# 12V_power_rail.net
KiCad netlist of a schematic drawn in EAGLE
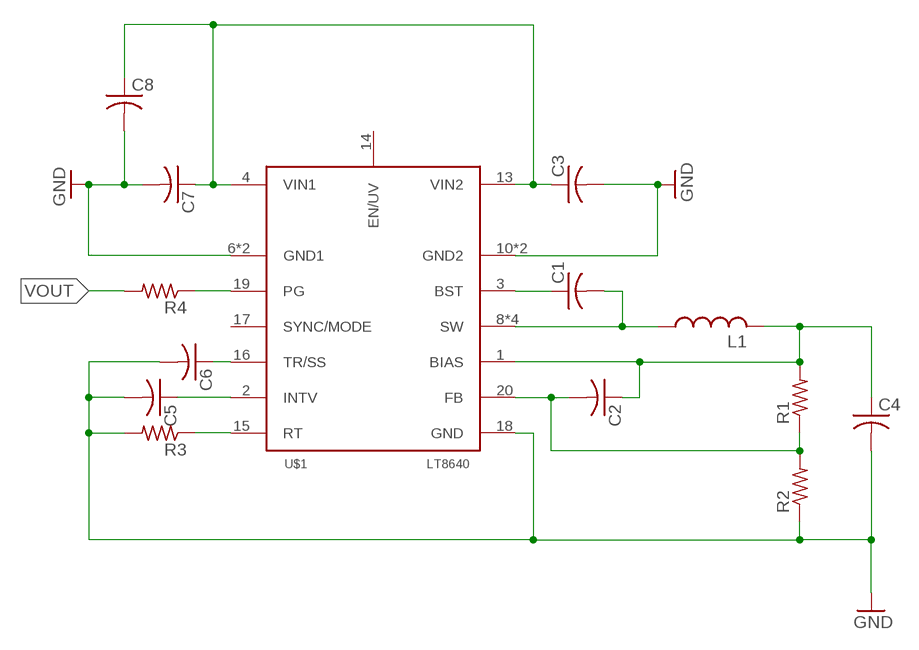
[diagram p0: schematic, sheet 1]

(export (version "E")
  (design (tool "Eeschema 10.0.6"))
  (components
    (comp (ref "C1")
      (value "C-USC0402")
      (footprint "eagle-import:C0402")
      (libsource (lib "eagle-import") (part "C-USC0402"))
    )
    (comp (ref "C2")
      (value "C-USC0402")
      (footprint "eagle-import:C0402")
      (libsource (lib "eagle-import") (part "C-USC0402"))
    )
    (comp (ref "C3")
      (value "C-USC0402")
      (footprint "eagle-import:C0402")
      (libsource (lib "eagle-import") (part "C-USC0402"))
    )
    (comp (ref "C4")
      (value "C-USC1210")
      (footprint "eagle-import:C1210")
      (libsource (lib "eagle-import") (part "C-USC1210"))
    )
    (comp (ref "C5")
      (value "C-USC0402")
      (footprint "eagle-import:C0402")
      (libsource (lib "eagle-import") (part "C-USC0402"))
    )
    (comp (ref "C6")
      (value "C-USC0402")
      (footprint "eagle-import:C0402")
      (libsource (lib "eagle-import") (part "C-USC0402"))
    )
    (comp (ref "C7")
      (value "C-USC0402")
      (footprint "eagle-import:C0402")
      (libsource (lib "eagle-import") (part "C-USC0402"))
    )
    (comp (ref "C8")
      (value "C-USC0603")
      (footprint "eagle-import:C0603")
      (libsource (lib "eagle-import") (part "C-USC0603"))
    )
    (comp (ref "L1")
      (value "L-USIHLP2525EZER4R7M01")
      (footprint "eagle-import:IHLP2525EZER4R7M01-FOOT")
      (libsource (lib "eagle-import") (part "L-USIHLP2525EZER4R7M01"))
    )
    (comp (ref "R1")
      (value "R-US_R0402")
      (footprint "eagle-import:R0402")
      (libsource (lib "eagle-import") (part "R-US_R0402"))
    )
    (comp (ref "R2")
      (value "R-US_R0402")
      (footprint "eagle-import:R0402")
      (libsource (lib "eagle-import") (part "R-US_R0402"))
    )
    (comp (ref "R3")
      (value "R-US_R0402")
      (footprint "eagle-import:R0402")
      (libsource (lib "eagle-import") (part "R-US_R0402"))
    )
    (comp (ref "R4")
      (value "R-US_R0402")
      (footprint "eagle-import:R0402")
      (libsource (lib "eagle-import") (part "R-US_R0402"))
    )
    (comp (ref "U$1")
      (value "LT8640")
      (footprint "eagle-import:LT8640_FOOT")
      (libsource (lib "eagle-import") (part "LT8640"))
    )
  )
  (nets
    (net (code "1") (name "GND") (class "Default")
      (node (ref "C3") (pin "2") (pinfunction "2_2") (pintype "passive"))
      (node (ref "C4") (pin "2") (pinfunction "2_2") (pintype "passive"))
      (node (ref "C5") (pin "2") (pinfunction "2_2") (pintype "passive"))
      (node (ref "C6") (pin "2") (pinfunction "2_2") (pintype "passive"))
      (node (ref "C7") (pin "2") (pinfunction "2_2") (pintype "passive"))
      (node (ref "C8") (pin "2") (pinfunction "2_2") (pintype "passive"))
      (node (ref "R2") (pin "1") (pinfunction "1_1") (pintype "passive"))
      (node (ref "R3") (pin "2") (pinfunction "2_2") (pintype "passive"))
      (node (ref "U$1") (pin "10") (pinfunction "GND2_10") (pintype "bidirectional"))
      (node (ref "U$1") (pin "11") (pinfunction "GND2_11") (pintype "bidirectional"))
      (node (ref "U$1") (pin "18") (pinfunction "GND_18") (pintype "bidirectional"))
      (node (ref "U$1") (pin "6") (pinfunction "GND1_6") (pintype "bidirectional"))
      (node (ref "U$1") (pin "7") (pinfunction "GND1_7") (pintype "bidirectional"))
    )
    (net (code "2") (name "Net-(C1-Pad2)") (class "Default")
      (node (ref "C1") (pin "2") (pinfunction "2_2") (pintype "passive"))
      (node (ref "L1") (pin "1") (pinfunction "1_1") (pintype "passive"))
      (node (ref "U$1") (pin "21") (pinfunction "SW_21") (pintype "bidirectional"))
      (node (ref "U$1") (pin "22") (pinfunction "SW_22") (pintype "bidirectional"))
      (node (ref "U$1") (pin "8") (pinfunction "SW_8") (pintype "bidirectional"))
      (node (ref "U$1") (pin "9") (pinfunction "SW_9") (pintype "bidirectional"))
    )
    (net (code "3") (name "Net-(U$1-BST)") (class "Default")
      (node (ref "C1") (pin "1") (pinfunction "1_1") (pintype "passive"))
      (node (ref "U$1") (pin "3") (pinfunction "BST_3") (pintype "bidirectional"))
    )
    (net (code "4") (name "Net-(U$1-FB)") (class "Default")
      (node (ref "C2") (pin "2") (pinfunction "2_2") (pintype "passive"))
      (node (ref "R1") (pin "1") (pinfunction "1_1") (pintype "passive"))
      (node (ref "R2") (pin "2") (pinfunction "2_2") (pintype "passive"))
      (node (ref "U$1") (pin "20") (pinfunction "FB_20") (pintype "bidirectional"))
    )
    (net (code "5") (name "Net-(U$1-INTV)") (class "Default")
      (node (ref "C5") (pin "1") (pinfunction "1_1") (pintype "passive"))
      (node (ref "U$1") (pin "2") (pinfunction "INTV_2") (pintype "bidirectional"))
    )
    (net (code "6") (name "Net-(U$1-PG)") (class "Default")
      (node (ref "R4") (pin "1") (pinfunction "1_1") (pintype "passive"))
      (node (ref "U$1") (pin "19") (pinfunction "PG_19") (pintype "bidirectional"))
    )
    (net (code "7") (name "Net-(U$1-RT)") (class "Default")
      (node (ref "R3") (pin "1") (pinfunction "1_1") (pintype "passive"))
      (node (ref "U$1") (pin "15") (pinfunction "RT_15") (pintype "bidirectional"))
    )
    (net (code "8") (name "Net-(U$1-TR{slash}SS)") (class "Default")
      (node (ref "C6") (pin "1") (pinfunction "1_1") (pintype "passive"))
      (node (ref "U$1") (pin "16") (pinfunction "TR/SS_16") (pintype "bidirectional"))
    )
    (net (code "9") (name "Net-(U$1-VIN1)") (class "Default")
      (node (ref "C3") (pin "1") (pinfunction "1_1") (pintype "passive"))
      (node (ref "C7") (pin "1") (pinfunction "1_1") (pintype "passive"))
      (node (ref "C8") (pin "1") (pinfunction "1_1") (pintype "passive"))
      (node (ref "U$1") (pin "13") (pinfunction "VIN2_13") (pintype "bidirectional"))
      (node (ref "U$1") (pin "4") (pinfunction "VIN1_4") (pintype "bidirectional"))
    )
    (net (code "10") (name "VOUT") (class "Default")
      (node (ref "C2") (pin "1") (pinfunction "1_1") (pintype "passive"))
      (node (ref "C4") (pin "1") (pinfunction "1_1") (pintype "passive"))
      (node (ref "L1") (pin "2") (pinfunction "2_2") (pintype "passive"))
      (node (ref "R1") (pin "2") (pinfunction "2_2") (pintype "passive"))
      (node (ref "R4") (pin "2") (pinfunction "2_2") (pintype "passive"))
      (node (ref "U$1") (pin "1") (pinfunction "BIAS_1") (pintype "bidirectional"))
    )
    (net (code "11") (name "unconnected-(U$1-EN{slash}UV-Pad14)") (class "Default")
      (node (ref "U$1") (pin "14") (pinfunction "EN/UV_14") (pintype "bidirectional"))
    )
    (net (code "12") (name "unconnected-(U$1-SYNC{slash}MODE-Pad17)") (class "Default")
      (node (ref "U$1") (pin "17") (pinfunction "SYNC/MODE_17") (pintype "bidirectional"))
    )
  )
)
